# main.net
KiCad netlist of a schematic drawn in EAGLE
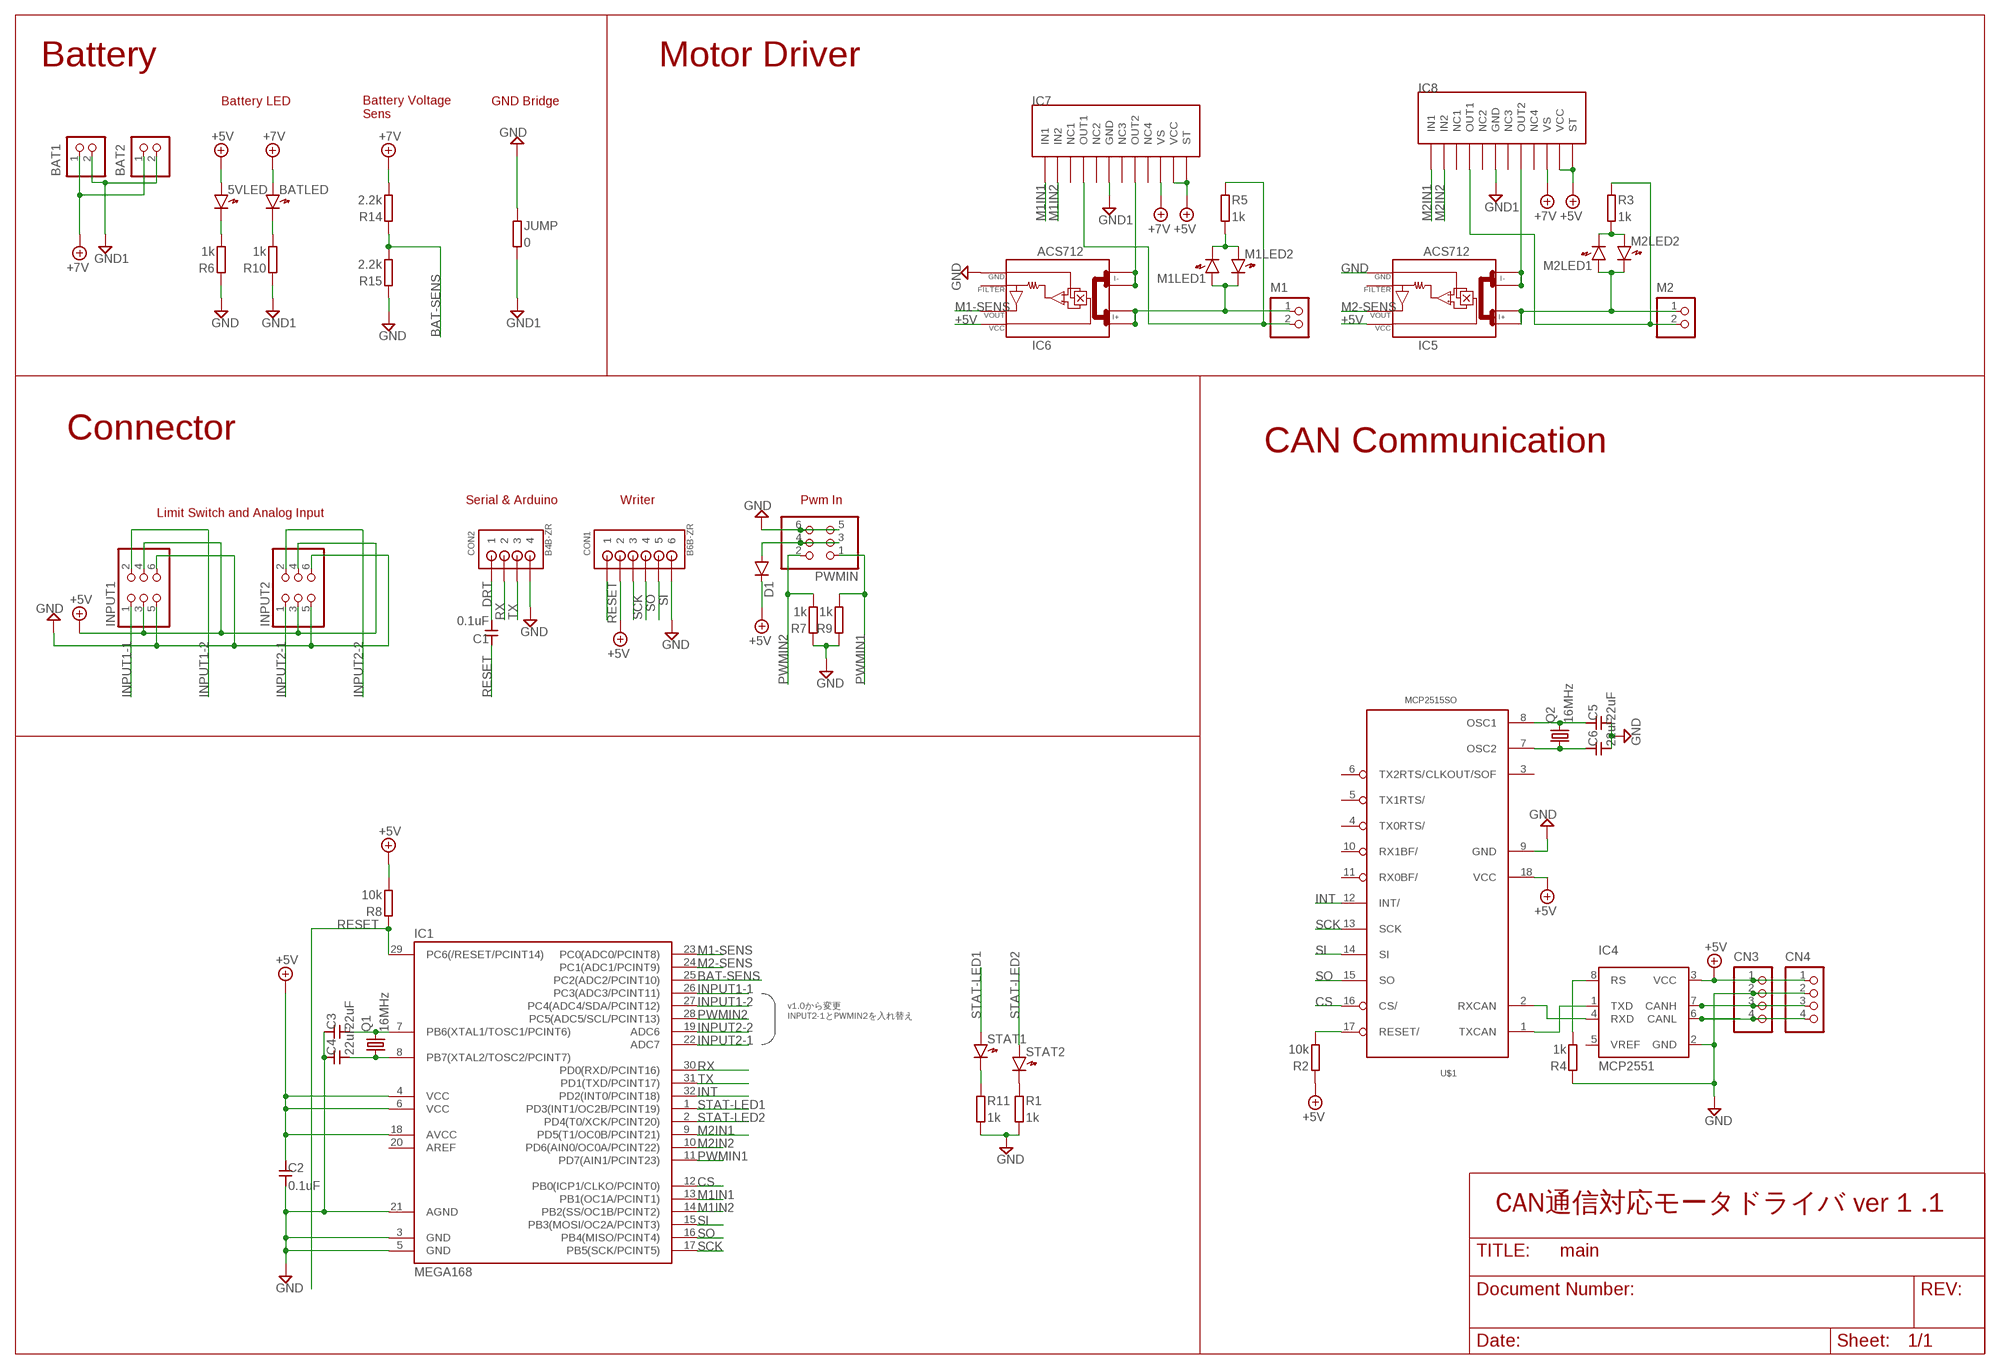
[diagram p0: schematic, sheet 1]

(export (version "E")
  (design (tool "Eeschema 10.0.6"))
  (components
    (comp (ref "5VLED")
      (value "LED2012")
      (footprint "eagle-import:LED2012")
      (libsource (lib "eagle-import") (part "LED2012"))
    )
    (comp (ref "BAT1")
      (value "B2P-VH")
      (footprint "eagle-import:B2P-VH")
      (libsource (lib "eagle-import") (part "B2P-VH"))
    )
    (comp (ref "BAT2")
      (value "B2P-VH")
      (footprint "eagle-import:B2P-VH")
      (libsource (lib "eagle-import") (part "B2P-VH"))
    )
    (comp (ref "BATLED")
      (value "LED2012")
      (footprint "eagle-import:LED2012")
      (libsource (lib "eagle-import") (part "LED2012"))
    )
    (comp (ref "C1")
      (value "0.1uF")
      (footprint "eagle-import:SMD2012")
      (libsource (lib "eagle-import") (part "CAPACITOR2012"))
    )
    (comp (ref "C2")
      (value "0.1uF")
      (footprint "eagle-import:SMD2012")
      (libsource (lib "eagle-import") (part "CAPACITOR2012"))
    )
    (comp (ref "C3")
      (value "22uF")
      (footprint "eagle-import:SMD2012")
      (libsource (lib "eagle-import") (part "CAPACITOR2012"))
    )
    (comp (ref "C4")
      (value "22uF")
      (footprint "eagle-import:SMD2012")
      (libsource (lib "eagle-import") (part "CAPACITOR2012"))
    )
    (comp (ref "C5")
      (value "22uF")
      (footprint "eagle-import:SMD2012")
      (libsource (lib "eagle-import") (part "CAPACITOR2012"))
    )
    (comp (ref "C6")
      (value "22uF")
      (footprint "eagle-import:SMD2012")
      (libsource (lib "eagle-import") (part "CAPACITOR2012"))
    )
    (comp (ref "CN3")
      (value "B4B-PH-K-S")
      (footprint "eagle-import:B4B-PH-K-S")
      (libsource (lib "eagle-import") (part "B4B-PH-K-S"))
    )
    (comp (ref "CN4")
      (value "B4B-PH-K-S")
      (footprint "eagle-import:B4B-PH-K-S")
      (libsource (lib "eagle-import") (part "B4B-PH-K-S"))
    )
    (comp (ref "CON1")
      (value "B6B-ZR")
      (footprint "eagle-import:B6B-ZR")
      (libsource (lib "eagle-import") (part "B6B-ZR"))
    )
    (comp (ref "CON2")
      (value "B4B-ZR")
      (footprint "eagle-import:B4B-ZR")
      (libsource (lib "eagle-import") (part "B4B-ZR"))
    )
    (comp (ref "D1")
      (value "DIODESOD123")
      (footprint "eagle-import:SOD-123")
      (libsource (lib "eagle-import") (part "DIODESOD123"))
    )
    (comp (ref "IC1")
      (value "MEGA168")
      (footprint "eagle-import:TQFP32-08")
      (libsource (lib "eagle-import") (part "MEGA48/88/168-AU"))
    )
    (comp (ref "IC4")
      (value "MCP2551")
      (footprint "eagle-import:SOIC")
      (libsource (lib "eagle-import") (part "MCP2551"))
    )
    (comp (ref "IC5")
      (value "ACS712")
      (footprint "eagle-import:SO08")
      (libsource (lib "eagle-import") (part "ACS712"))
    )
    (comp (ref "IC6")
      (value "ACS712")
      (footprint "eagle-import:SO08")
      (libsource (lib "eagle-import") (part "ACS712"))
    )
    (comp (ref "IC7")
      (value "TA8429H")
      (footprint "eagle-import:TA8429H")
      (libsource (lib "eagle-import") (part "TA8429H"))
    )
    (comp (ref "IC8")
      (value "TA8429H")
      (footprint "eagle-import:TA8429H")
      (libsource (lib "eagle-import") (part "TA8429H"))
    )
    (comp (ref "INPUT1")
      (value "PINHD-2X3")
      (footprint "eagle-import:2X03")
      (libsource (lib "eagle-import") (part "PINHD-2X3"))
    )
    (comp (ref "INPUT2")
      (value "PINHD-2X3")
      (footprint "eagle-import:2X03")
      (libsource (lib "eagle-import") (part "PINHD-2X3"))
    )
    (comp (ref "JUMP")
      (value "0")
      (footprint "eagle-import:SMD2012")
      (libsource (lib "eagle-import") (part "RESISTOR2012"))
    )
    (comp (ref "M1")
      (value "B2P-VH")
      (footprint "eagle-import:B2P-VH")
      (libsource (lib "eagle-import") (part "B2P-VH"))
    )
    (comp (ref "M1LED1")
      (value "LED2012")
      (footprint "eagle-import:LED2012")
      (libsource (lib "eagle-import") (part "LED2012"))
    )
    (comp (ref "M1LED2")
      (value "LED2012")
      (footprint "eagle-import:LED2012")
      (libsource (lib "eagle-import") (part "LED2012"))
    )
    (comp (ref "M2")
      (value "B2P-VH")
      (footprint "eagle-import:B2P-VH")
      (libsource (lib "eagle-import") (part "B2P-VH"))
    )
    (comp (ref "M2LED1")
      (value "LED2012")
      (footprint "eagle-import:LED2012")
      (libsource (lib "eagle-import") (part "LED2012"))
    )
    (comp (ref "M2LED2")
      (value "LED2012")
      (footprint "eagle-import:LED2012")
      (libsource (lib "eagle-import") (part "LED2012"))
    )
    (comp (ref "PWMIN")
      (value "PINHD-2X3")
      (footprint "eagle-import:2X03")
      (libsource (lib "eagle-import") (part "PINHD-2X3"))
    )
    (comp (ref "Q1")
      (value "16MHz")
      (footprint "eagle-import:HC49_S")
      (libsource (lib "eagle-import") (part "CRYSTALHC49S"))
    )
    (comp (ref "Q2")
      (value "16MHz")
      (footprint "eagle-import:HC49_S")
      (libsource (lib "eagle-import") (part "CRYSTALHC49S"))
    )
    (comp (ref "R1")
      (value "1k")
      (footprint "eagle-import:SMD2012")
      (libsource (lib "eagle-import") (part "RESISTOR2012"))
    )
    (comp (ref "R2")
      (value "10k")
      (footprint "eagle-import:SMD2012")
      (libsource (lib "eagle-import") (part "RESISTOR2012"))
    )
    (comp (ref "R3")
      (value "1k")
      (footprint "eagle-import:SMD2012")
      (libsource (lib "eagle-import") (part "RESISTOR2012"))
    )
    (comp (ref "R4")
      (value "1k")
      (footprint "eagle-import:SMD2012")
      (libsource (lib "eagle-import") (part "RESISTOR2012"))
    )
    (comp (ref "R5")
      (value "1k")
      (footprint "eagle-import:SMD2012")
      (libsource (lib "eagle-import") (part "RESISTOR2012"))
    )
    (comp (ref "R6")
      (value "1k")
      (footprint "eagle-import:SMD2012")
      (libsource (lib "eagle-import") (part "RESISTOR2012"))
    )
    (comp (ref "R7")
      (value "1k")
      (footprint "eagle-import:SMD2012")
      (libsource (lib "eagle-import") (part "RESISTOR2012"))
    )
    (comp (ref "R8")
      (value "10k")
      (footprint "eagle-import:SMD2012")
      (libsource (lib "eagle-import") (part "RESISTOR2012"))
    )
    (comp (ref "R9")
      (value "1k")
      (footprint "eagle-import:SMD2012")
      (libsource (lib "eagle-import") (part "RESISTOR2012"))
    )
    (comp (ref "R10")
      (value "1k")
      (footprint "eagle-import:SMD2012")
      (libsource (lib "eagle-import") (part "RESISTOR2012"))
    )
    (comp (ref "R11")
      (value "1k")
      (footprint "eagle-import:SMD2012")
      (libsource (lib "eagle-import") (part "RESISTOR2012"))
    )
    (comp (ref "R14")
      (value "2.2k")
      (footprint "eagle-import:SMD2012")
      (libsource (lib "eagle-import") (part "RESISTOR2012"))
    )
    (comp (ref "R15")
      (value "2.2k")
      (footprint "eagle-import:SMD2012")
      (libsource (lib "eagle-import") (part "RESISTOR2012"))
    )
    (comp (ref "STAT1")
      (value "LED2012")
      (footprint "eagle-import:LED2012")
      (libsource (lib "eagle-import") (part "LED2012"))
    )
    (comp (ref "STAT2")
      (value "LED2012")
      (footprint "eagle-import:LED2012")
      (libsource (lib "eagle-import") (part "LED2012"))
    )
    (comp (ref "U$1")
      (value "MCP2515SO")
      (footprint "eagle-import:SO18L")
      (libsource (lib "eagle-import") (part "MCP2515SO"))
    )
  )
  (nets
    (net (code "1") (name "+5V") (class "Default")
      (node (ref "5VLED") (pin "A") (pinfunction "A_A") (pintype "passive"))
      (node (ref "C2") (pin "1") (pinfunction "1_1") (pintype "passive"))
      (node (ref "CN3") (pin "1") (pinfunction "1_1") (pintype "passive"))
      (node (ref "CN4") (pin "1") (pinfunction "1_1") (pintype "passive"))
      (node (ref "CON1") (pin "2") (pinfunction "2_2") (pintype "bidirectional"))
      (node (ref "D1") (pin "C") (pinfunction "C_C") (pintype "passive"))
      (node (ref "IC1") (pin "18") (pinfunction "AVCC_18") (pintype "passive"))
      (node (ref "IC1") (pin "4") (pinfunction "VCC_4") (pintype "power_in"))
      (node (ref "IC1") (pin "6") (pinfunction "VCC_6") (pintype "power_in"))
      (node (ref "IC4") (pin "3") (pinfunction "VCC_3") (pintype "power_in"))
      (node (ref "IC5") (pin "8") (pinfunction "VCC_8") (pintype "power_in"))
      (node (ref "IC6") (pin "8") (pinfunction "VCC_8") (pintype "power_in"))
      (node (ref "IC7") (pin "P$11") (pinfunction "VCC_P$11") (pintype "bidirectional"))
      (node (ref "IC7") (pin "P$12") (pinfunction "ST_P$12") (pintype "bidirectional"))
      (node (ref "IC8") (pin "P$11") (pinfunction "VCC_P$11") (pintype "bidirectional"))
      (node (ref "IC8") (pin "P$12") (pinfunction "ST_P$12") (pintype "bidirectional"))
      (node (ref "INPUT1") (pin "3") (pinfunction "3_3") (pintype "passive"))
      (node (ref "INPUT1") (pin "4") (pinfunction "4_4") (pintype "passive"))
      (node (ref "INPUT2") (pin "3") (pinfunction "3_3") (pintype "passive"))
      (node (ref "INPUT2") (pin "4") (pinfunction "4_4") (pintype "passive"))
      (node (ref "R2") (pin "1") (pinfunction "1_1") (pintype "passive"))
      (node (ref "R8") (pin "2") (pinfunction "2_2") (pintype "passive"))
      (node (ref "U$1") (pin "18") (pinfunction "VCC_18") (pintype "power_in"))
    )
    (net (code "2") (name "+7V") (class "Default")
      (node (ref "BAT1") (pin "1") (pinfunction "1_1") (pintype "passive"))
      (node (ref "BAT2") (pin "1") (pinfunction "1_1") (pintype "passive"))
      (node (ref "BATLED") (pin "A") (pinfunction "A_A") (pintype "passive"))
      (node (ref "IC7") (pin "P$10") (pinfunction "VS_P$10") (pintype "bidirectional"))
      (node (ref "IC8") (pin "P$10") (pinfunction "VS_P$10") (pintype "bidirectional"))
      (node (ref "R14") (pin "2") (pinfunction "2_2") (pintype "passive"))
    )
    (net (code "3") (name "/BAT-SENS") (class "Default")
      (node (ref "IC1") (pin "25") (pinfunction "PC2(ADC2/PCINT10)_25") (pintype "bidirectional"))
      (node (ref "R14") (pin "1") (pinfunction "1_1") (pintype "passive"))
      (node (ref "R15") (pin "2") (pinfunction "2_2") (pintype "passive"))
    )
    (net (code "4") (name "/CS") (class "Default")
      (node (ref "IC1") (pin "12") (pinfunction "PB0(ICP1/CLKO/PCINT0)_12") (pintype "bidirectional"))
      (node (ref "U$1") (pin "16") (pinfunction "CS/_16") (pintype "input"))
    )
    (net (code "5") (name "/DRT") (class "Default")
      (node (ref "C1") (pin "2") (pinfunction "2_2") (pintype "passive"))
      (node (ref "CON2") (pin "1") (pinfunction "1_1") (pintype "bidirectional"))
    )
    (net (code "6") (name "/INPUT1-1") (class "Default")
      (node (ref "IC1") (pin "26") (pinfunction "PC3(ADC3/PCINT11)_26") (pintype "bidirectional"))
      (node (ref "INPUT1") (pin "1") (pinfunction "1_1") (pintype "passive"))
    )
    (net (code "7") (name "/INPUT1-2") (class "Default")
      (node (ref "IC1") (pin "27") (pinfunction "PC4(ADC4/SDA/PCINT12)_27") (pintype "bidirectional"))
      (node (ref "INPUT1") (pin "2") (pinfunction "2_2") (pintype "passive"))
    )
    (net (code "8") (name "/INPUT2-1") (class "Default")
      (node (ref "IC1") (pin "22") (pinfunction "ADC7_22") (pintype "passive"))
      (node (ref "INPUT2") (pin "1") (pinfunction "1_1") (pintype "passive"))
    )
    (net (code "9") (name "/INPUT2-2") (class "Default")
      (node (ref "IC1") (pin "19") (pinfunction "ADC6_19") (pintype "passive"))
      (node (ref "INPUT2") (pin "2") (pinfunction "2_2") (pintype "passive"))
    )
    (net (code "10") (name "/INT") (class "Default")
      (node (ref "IC1") (pin "32") (pinfunction "PD2(INT0/PCINT18)_32") (pintype "bidirectional"))
      (node (ref "U$1") (pin "12") (pinfunction "INT/_12") (pintype "output"))
    )
    (net (code "11") (name "/M1-SENS") (class "Default")
      (node (ref "IC1") (pin "23") (pinfunction "PC0(ADC0/PCINT8)_23") (pintype "bidirectional"))
      (node (ref "IC6") (pin "7") (pinfunction "VOUT_7") (pintype "output"))
    )
    (net (code "12") (name "/M1IN1") (class "Default")
      (node (ref "IC1") (pin "13") (pinfunction "PB1(OC1A/PCINT1)_13") (pintype "bidirectional"))
      (node (ref "IC7") (pin "P$1") (pinfunction "IN1_P$1") (pintype "bidirectional"))
    )
    (net (code "13") (name "/M1IN2") (class "Default")
      (node (ref "IC1") (pin "14") (pinfunction "PB2(SS/OC1B/PCINT2)_14") (pintype "bidirectional"))
      (node (ref "IC7") (pin "P$2") (pinfunction "IN2_P$2") (pintype "bidirectional"))
    )
    (net (code "14") (name "/M2-SENS") (class "Default")
      (node (ref "IC1") (pin "24") (pinfunction "PC1(ADC1/PCINT9)_24") (pintype "bidirectional"))
      (node (ref "IC5") (pin "7") (pinfunction "VOUT_7") (pintype "output"))
    )
    (net (code "15") (name "/M2IN1") (class "Default")
      (node (ref "IC1") (pin "9") (pinfunction "PD5(T1/OC0B/PCINT21)_9") (pintype "bidirectional"))
      (node (ref "IC8") (pin "P$1") (pinfunction "IN1_P$1") (pintype "bidirectional"))
    )
    (net (code "16") (name "/M2IN2") (class "Default")
      (node (ref "IC1") (pin "10") (pinfunction "PD6(AIN0/OC0A/PCINT22)_10") (pintype "bidirectional"))
      (node (ref "IC8") (pin "P$2") (pinfunction "IN2_P$2") (pintype "bidirectional"))
    )
    (net (code "17") (name "/PWMIN1") (class "Default")
      (node (ref "IC1") (pin "11") (pinfunction "PD7(AIN1/PCINT23)_11") (pintype "bidirectional"))
      (node (ref "PWMIN") (pin "1") (pinfunction "1_1") (pintype "passive"))
      (node (ref "R9") (pin "2") (pinfunction "2_2") (pintype "passive"))
    )
    (net (code "18") (name "/PWMIN2") (class "Default")
      (node (ref "IC1") (pin "28") (pinfunction "PC5(ADC5/SCL/PCINT13)_28") (pintype "bidirectional"))
      (node (ref "PWMIN") (pin "2") (pinfunction "2_2") (pintype "passive"))
      (node (ref "R7") (pin "2") (pinfunction "2_2") (pintype "passive"))
    )
    (net (code "19") (name "/RESET") (class "Default")
      (node (ref "C1") (pin "1") (pinfunction "1_1") (pintype "passive"))
      (node (ref "CON1") (pin "1") (pinfunction "1_1") (pintype "bidirectional"))
      (node (ref "IC1") (pin "29") (pinfunction "PC6(/RESET/PCINT14)_29") (pintype "bidirectional"))
      (node (ref "R8") (pin "1") (pinfunction "1_1") (pintype "passive"))
    )
    (net (code "20") (name "/RX") (class "Default")
      (node (ref "CON2") (pin "2") (pinfunction "2_2") (pintype "bidirectional"))
      (node (ref "IC1") (pin "30") (pinfunction "PD0(RXD/PCINT16)_30") (pintype "bidirectional"))
    )
    (net (code "21") (name "/SCK") (class "Default")
      (node (ref "CON1") (pin "3") (pinfunction "3_3") (pintype "bidirectional"))
      (node (ref "IC1") (pin "17") (pinfunction "PB5(SCK/PCINT5)_17") (pintype "bidirectional"))
      (node (ref "U$1") (pin "13") (pinfunction "SCK_13") (pintype "input"))
    )
    (net (code "22") (name "/SI") (class "Default")
      (node (ref "CON1") (pin "5") (pinfunction "5_5") (pintype "bidirectional"))
      (node (ref "IC1") (pin "15") (pinfunction "PB3(MOSI/OC2A/PCINT3)_15") (pintype "bidirectional"))
      (node (ref "U$1") (pin "14") (pinfunction "SI_14") (pintype "input"))
    )
    (net (code "23") (name "/SO") (class "Default")
      (node (ref "CON1") (pin "4") (pinfunction "4_4") (pintype "bidirectional"))
      (node (ref "IC1") (pin "16") (pinfunction "PB4(MISO/PCINT4)_16") (pintype "bidirectional"))
      (node (ref "U$1") (pin "15") (pinfunction "SO_15") (pintype "output"))
    )
    (net (code "24") (name "/STAT-LED1") (class "Default")
      (node (ref "IC1") (pin "1") (pinfunction "PD3(INT1/OC2B/PCINT19)_1") (pintype "bidirectional"))
      (node (ref "STAT1") (pin "A") (pinfunction "A_A") (pintype "passive"))
    )
    (net (code "25") (name "/STAT-LED2") (class "Default")
      (node (ref "IC1") (pin "2") (pinfunction "PD4(T0/XCK/PCINT20)_2") (pintype "bidirectional"))
      (node (ref "STAT2") (pin "A") (pinfunction "A_A") (pintype "passive"))
    )
    (net (code "26") (name "/TX") (class "Default")
      (node (ref "CON2") (pin "3") (pinfunction "3_3") (pintype "bidirectional"))
      (node (ref "IC1") (pin "31") (pinfunction "PD1(TXD/PCINT17)_31") (pintype "bidirectional"))
    )
    (net (code "27") (name "GND") (class "Default")
      (node (ref "C2") (pin "2") (pinfunction "2_2") (pintype "passive"))
      (node (ref "C3") (pin "1") (pinfunction "1_1") (pintype "passive"))
      (node (ref "C4") (pin "1") (pinfunction "1_1") (pintype "passive"))
      (node (ref "C5") (pin "2") (pinfunction "2_2") (pintype "passive"))
      (node (ref "C6") (pin "2") (pinfunction "2_2") (pintype "passive"))
      (node (ref "CN3") (pin "2") (pinfunction "2_2") (pintype "passive"))
      (node (ref "CN4") (pin "2") (pinfunction "2_2") (pintype "passive"))
      (node (ref "CON1") (pin "6") (pinfunction "6_6") (pintype "bidirectional"))
      (node (ref "CON2") (pin "4") (pinfunction "4_4") (pintype "bidirectional"))
      (node (ref "IC1") (pin "21") (pinfunction "AGND_21") (pintype "power_in"))
      (node (ref "IC1") (pin "3") (pinfunction "GND_3") (pintype "power_in"))
      (node (ref "IC1") (pin "5") (pinfunction "GND_5") (pintype "power_in"))
      (node (ref "IC4") (pin "2") (pinfunction "GND_2") (pintype "power_in"))
      (node (ref "IC5") (pin "5") (pinfunction "GND_5") (pintype "power_in"))
      (node (ref "IC6") (pin "5") (pinfunction "GND_5") (pintype "power_in"))
      (node (ref "INPUT1") (pin "5") (pinfunction "5_5") (pintype "passive"))
      (node (ref "INPUT1") (pin "6") (pinfunction "6_6") (pintype "passive"))
      (node (ref "INPUT2") (pin "5") (pinfunction "5_5") (pintype "passive"))
      (node (ref "INPUT2") (pin "6") (pinfunction "6_6") (pintype "passive"))
      (node (ref "JUMP") (pin "1") (pinfunction "1_1") (pintype "passive"))
      (node (ref "PWMIN") (pin "5") (pinfunction "5_5") (pintype "passive"))
      (node (ref "PWMIN") (pin "6") (pinfunction "6_6") (pintype "passive"))
      (node (ref "R1") (pin "2") (pinfunction "2_2") (pintype "passive"))
      (node (ref "R11") (pin "2") (pinfunction "2_2") (pintype "passive"))
      (node (ref "R15") (pin "1") (pinfunction "1_1") (pintype "passive"))
      (node (ref "R4") (pin "1") (pinfunction "1_1") (pintype "passive"))
      (node (ref "R6") (pin "1") (pinfunction "1_1") (pintype "passive"))
      (node (ref "R7") (pin "1") (pinfunction "1_1") (pintype "passive"))
      (node (ref "R9") (pin "1") (pinfunction "1_1") (pintype "passive"))
      (node (ref "U$1") (pin "9") (pinfunction "GND_9") (pintype "power_in"))
    )
    (net (code "28") (name "GND1") (class "Default")
      (node (ref "BAT1") (pin "2") (pinfunction "2_2") (pintype "passive"))
      (node (ref "BAT2") (pin "2") (pinfunction "2_2") (pintype "passive"))
      (node (ref "IC7") (pin "P$6") (pinfunction "GND_P$6") (pintype "bidirectional"))
      (node (ref "IC8") (pin "P$6") (pinfunction "GND_P$6") (pintype "bidirectional"))
      (node (ref "JUMP") (pin "2") (pinfunction "2_2") (pintype "passive"))
      (node (ref "R10") (pin "1") (pinfunction "1_1") (pintype "passive"))
    )
    (net (code "29") (name "Net-(5VLED-PadK)") (class "Default")
      (node (ref "5VLED") (pin "K") (pinfunction "K_K") (pintype "passive"))
      (node (ref "R6") (pin "2") (pinfunction "2_2") (pintype "passive"))
    )
    (net (code "30") (name "Net-(BATLED-PadK)") (class "Default")
      (node (ref "BATLED") (pin "K") (pinfunction "K_K") (pintype "passive"))
      (node (ref "R10") (pin "2") (pinfunction "2_2") (pintype "passive"))
    )
    (net (code "31") (name "Net-(D1-PadA)") (class "Default")
      (node (ref "D1") (pin "A") (pinfunction "A_A") (pintype "passive"))
      (node (ref "PWMIN") (pin "3") (pinfunction "3_3") (pintype "passive"))
      (node (ref "PWMIN") (pin "4") (pinfunction "4_4") (pintype "passive"))
    )
    (net (code "32") (name "Net-(IC1-PB6(XTAL1{slash}TOSC1{slash}PCINT6))") (class "Default")
      (node (ref "C3") (pin "2") (pinfunction "2_2") (pintype "passive"))
      (node (ref "IC1") (pin "7") (pinfunction "PB6(XTAL1/TOSC1/PCINT6)_7") (pintype "bidirectional"))
      (node (ref "Q1") (pin "2") (pinfunction "2_2") (pintype "passive"))
    )
    (net (code "33") (name "Net-(IC1-PB7(XTAL2{slash}TOSC2{slash}PCINT7))") (class "Default")
      (node (ref "C4") (pin "2") (pinfunction "2_2") (pintype "passive"))
      (node (ref "IC1") (pin "8") (pinfunction "PB7(XTAL2/TOSC2/PCINT7)_8") (pintype "bidirectional"))
      (node (ref "Q1") (pin "1") (pinfunction "1_1") (pintype "passive"))
    )
    (net (code "34") (name "Net-(IC4-CANH)") (class "Default")
      (node (ref "CN3") (pin "3") (pinfunction "3_3") (pintype "passive"))
      (node (ref "CN4") (pin "3") (pinfunction "3_3") (pintype "passive"))
      (node (ref "IC4") (pin "7") (pinfunction "CANH_7") (pintype "bidirectional"))
    )
    (net (code "35") (name "Net-(IC4-CANL)") (class "Default")
      (node (ref "CN3") (pin "4") (pinfunction "4_4") (pintype "passive"))
      (node (ref "CN4") (pin "4") (pinfunction "4_4") (pintype "passive"))
      (node (ref "IC4") (pin "6") (pinfunction "CANL_6") (pintype "bidirectional"))
    )
    (net (code "36") (name "Net-(IC4-RS)") (class "Default")
      (node (ref "IC4") (pin "8") (pinfunction "RS_8") (pintype "bidirectional"))
      (node (ref "R4") (pin "2") (pinfunction "2_2") (pintype "passive"))
    )
    (net (code "37") (name "Net-(IC4-RXD)") (class "Default")
      (node (ref "IC4") (pin "4") (pinfunction "RXD_4") (pintype "bidirectional"))
      (node (ref "U$1") (pin "2") (pinfunction "RXCAN_2") (pintype "input"))
    )
    (net (code "38") (name "Net-(IC4-TXD)") (class "Default")
      (node (ref "IC4") (pin "1") (pinfunction "TXD_1") (pintype "bidirectional"))
      (node (ref "U$1") (pin "1") (pinfunction "TXCAN_1") (pintype "output"))
    )
    (net (code "39") (name "Net-(IC5-I+_0)") (class "Default")
      (node (ref "IC5") (pin "1") (pinfunction "I+_0_1") (pintype "bidirectional"))
      (node (ref "IC5") (pin "2") (pinfunction "I+_1_2") (pintype "bidirectional"))
      (node (ref "M2") (pin "1") (pinfunction "1_1") (pintype "passive"))
      (node (ref "M2LED1") (pin "A") (pinfunction "A_A") (pintype "passive"))
      (node (ref "M2LED2") (pin "K") (pinfunction "K_K") (pintype "passive"))
    )
    (net (code "40") (name "Net-(IC5-I-_0)") (class "Default")
      (node (ref "IC5") (pin "3") (pinfunction "I-_0_3") (pintype "bidirectional"))
      (node (ref "IC5") (pin "4") (pinfunction "I-_1_4") (pintype "bidirectional"))
      (node (ref "IC8") (pin "P$8") (pinfunction "OUT2_P$8") (pintype "bidirectional"))
    )
    (net (code "41") (name "Net-(IC6-I+_0)") (class "Default")
      (node (ref "IC6") (pin "1") (pinfunction "I+_0_1") (pintype "bidirectional"))
      (node (ref "IC6") (pin "2") (pinfunction "I+_1_2") (pintype "bidirectional"))
      (node (ref "M1") (pin "1") (pinfunction "1_1") (pintype "passive"))
      (node (ref "M1LED1") (pin "A") (pinfunction "A_A") (pintype "passive"))
      (node (ref "M1LED2") (pin "K") (pinfunction "K_K") (pintype "passive"))
    )
    (net (code "42") (name "Net-(IC6-I-_0)") (class "Default")
      (node (ref "IC6") (pin "3") (pinfunction "I-_0_3") (pintype "bidirectional"))
      (node (ref "IC6") (pin "4") (pinfunction "I-_1_4") (pintype "bidirectional"))
      (node (ref "IC7") (pin "P$8") (pinfunction "OUT2_P$8") (pintype "bidirectional"))
    )
    (net (code "43") (name "Net-(IC7-OUT1)") (class "Default")
      (node (ref "IC7") (pin "P$4") (pinfunction "OUT1_P$4") (pintype "bidirectional"))
      (node (ref "M1") (pin "2") (pinfunction "2_2") (pintype "passive"))
      (node (ref "R5") (pin "1") (pinfunction "1_1") (pintype "passive"))
    )
    (net (code "44") (name "Net-(IC8-OUT1)") (class "Default")
      (node (ref "IC8") (pin "P$4") (pinfunction "OUT1_P$4") (pintype "bidirectional"))
      (node (ref "M2") (pin "2") (pinfunction "2_2") (pintype "passive"))
      (node (ref "R3") (pin "1") (pinfunction "1_1") (pintype "passive"))
    )
    (net (code "45") (name "Net-(M1LED1-PadK)") (class "Default")
      (node (ref "M1LED1") (pin "K") (pinfunction "K_K") (pintype "passive"))
      (node (ref "M1LED2") (pin "A") (pinfunction "A_A") (pintype "passive"))
      (node (ref "R5") (pin "2") (pinfunction "2_2") (pintype "passive"))
    )
    (net (code "46") (name "Net-(M2LED1-PadK)") (class "Default")
      (node (ref "M2LED1") (pin "K") (pinfunction "K_K") (pintype "passive"))
      (node (ref "M2LED2") (pin "A") (pinfunction "A_A") (pintype "passive"))
      (node (ref "R3") (pin "2") (pinfunction "2_2") (pintype "passive"))
    )
    (net (code "47") (name "Net-(R1-Pad1)") (class "Default")
      (node (ref "R1") (pin "1") (pinfunction "1_1") (pintype "passive"))
      (node (ref "STAT2") (pin "K") (pinfunction "K_K") (pintype "passive"))
    )
    (net (code "48") (name "Net-(R11-Pad1)") (class "Default")
      (node (ref "R11") (pin "1") (pinfunction "1_1") (pintype "passive"))
      (node (ref "STAT1") (pin "K") (pinfunction "K_K") (pintype "passive"))
    )
    (net (code "49") (name "Net-(U$1-OSC1)") (class "Default")
      (node (ref "C5") (pin "1") (pinfunction "1_1") (pintype "passive"))
      (node (ref "Q2") (pin "2") (pinfunction "2_2") (pintype "passive"))
      (node (ref "U$1") (pin "8") (pinfunction "OSC1_8") (pintype "bidirectional"))
    )
    (net (code "50") (name "Net-(U$1-OSC2)") (class "Default")
      (node (ref "C6") (pin "1") (pinfunction "1_1") (pintype "passive"))
      (node (ref "Q2") (pin "1") (pinfunction "1_1") (pintype "passive"))
      (node (ref "U$1") (pin "7") (pinfunction "OSC2_7") (pintype "bidirectional"))
    )
    (net (code "51") (name "Net-(U$1-RESET{slash})") (class "Default")
      (node (ref "R2") (pin "2") (pinfunction "2_2") (pintype "passive"))
      (node (ref "U$1") (pin "17") (pinfunction "RESET/_17") (pintype "input"))
    )
    (net (code "52") (name "unconnected-(IC1-AREF-Pad20)") (class "Default")
      (node (ref "IC1") (pin "20") (pinfunction "AREF_20") (pintype "passive"))
    )
    (net (code "53") (name "unconnected-(IC4-VREF-Pad5)") (class "Default")
      (node (ref "IC4") (pin "5") (pinfunction "VREF_5") (pintype "bidirectional"))
    )
    (net (code "54") (name "unconnected-(IC5-FILTER-Pad6)") (class "Default")
      (node (ref "IC5") (pin "6") (pinfunction "FILTER_6") (pintype "bidirectional"))
    )
    (net (code "55") (name "unconnected-(IC6-FILTER-Pad6)") (class "Default")
      (node (ref "IC6") (pin "6") (pinfunction "FILTER_6") (pintype "bidirectional"))
    )
    (net (code "56") (name "unconnected-(IC7-NC1-PadP$3)") (class "Default")
      (node (ref "IC7") (pin "P$3") (pinfunction "NC1_P$3") (pintype "bidirectional"))
    )
    (net (code "57") (name "unconnected-(IC7-NC2-PadP$5)") (class "Default")
      (node (ref "IC7") (pin "P$5") (pinfunction "NC2_P$5") (pintype "bidirectional"))
    )
    (net (code "58") (name "unconnected-(IC7-NC3-PadP$7)") (class "Default")
      (node (ref "IC7") (pin "P$7") (pinfunction "NC3_P$7") (pintype "bidirectional"))
    )
    (net (code "59") (name "unconnected-(IC7-NC4-PadP$9)") (class "Default")
      (node (ref "IC7") (pin "P$9") (pinfunction "NC4_P$9") (pintype "bidirectional"))
    )
    (net (code "60") (name "unconnected-(IC8-NC1-PadP$3)") (class "Default")
      (node (ref "IC8") (pin "P$3") (pinfunction "NC1_P$3") (pintype "bidirectional"))
    )
    (net (code "61") (name "unconnected-(IC8-NC2-PadP$5)") (class "Default")
      (node (ref "IC8") (pin "P$5") (pinfunction "NC2_P$5") (pintype "bidirectional"))
    )
    (net (code "62") (name "unconnected-(IC8-NC3-PadP$7)") (class "Default")
      (node (ref "IC8") (pin "P$7") (pinfunction "NC3_P$7") (pintype "bidirectional"))
    )
    (net (code "63") (name "unconnected-(IC8-NC4-PadP$9)") (class "Default")
      (node (ref "IC8") (pin "P$9") (pinfunction "NC4_P$9") (pintype "bidirectional"))
    )
    (net (code "64") (name "unconnected-(U$1-CLKOUT{slash}SOF-Pad3)") (class "Default")
      (node (ref "U$1") (pin "3") (pinfunction "CLKOUT/SOF_3") (pintype "bidirectional"))
    )
    (net (code "65") (name "unconnected-(U$1-RX0BF{slash}-Pad11)") (class "Default")
      (node (ref "U$1") (pin "11") (pinfunction "RX0BF/_11") (pintype "bidirectional"))
    )
    (net (code "66") (name "unconnected-(U$1-RX1BF{slash}-Pad10)") (class "Default")
      (node (ref "U$1") (pin "10") (pinfunction "RX1BF/_10") (pintype "bidirectional"))
    )
    (net (code "67") (name "unconnected-(U$1-TX0RTS{slash}-Pad4)") (class "Default")
      (node (ref "U$1") (pin "4") (pinfunction "TX0RTS/_4") (pintype "bidirectional"))
    )
    (net (code "68") (name "unconnected-(U$1-TX1RTS{slash}-Pad5)") (class "Default")
      (node (ref "U$1") (pin "5") (pinfunction "TX1RTS/_5") (pintype "bidirectional"))
    )
    (net (code "69") (name "unconnected-(U$1-TX2RTS{slash}-Pad6)") (class "Default")
      (node (ref "U$1") (pin "6") (pinfunction "TX2RTS/_6") (pintype "bidirectional"))
    )
  )
)
